# Power_Supply_Switching.net
KiCad netlist of a schematic drawn in Altium Designer
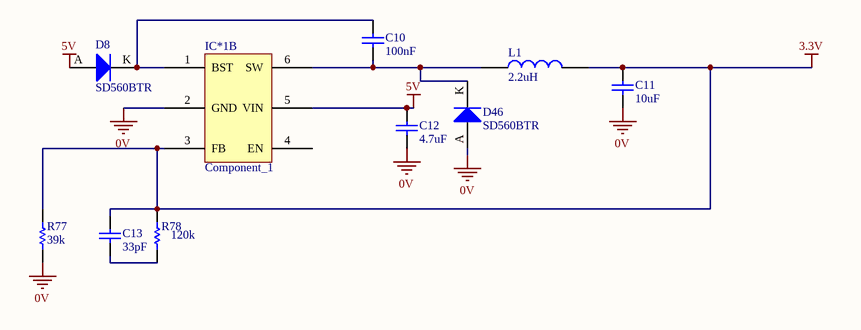
[diagram p0: Power Supply (Switching).SchDoc]

(export (version "E")
  (design (tool "Eeschema 10.0.6"))
  (components
    (comp (ref "C10")
      (value "100nF")
      (footprint "0805")
      (fields
        (field (name "PART NUMBER") "GCM21BR71E104KA37L")
        (field (name "TOLERANCE") "10%")
        (field (name "MANUFACTURER") "muRata")
      )
      (libsource (lib "ts_19-standard-library-IED") (part "Capacitor"))
    )
    (comp (ref "C11")
      (value "10uF")
      (footprint "0805")
      (fields
        (field (name "PART NUMBER") "GCM21BR61A106KA37L")
        (field (name "TOLERANCE") "10%")
        (field (name "MANUFACTURER") "muRata")
      )
      (libsource (lib "ts_19-standard-library-IED") (part "Capacitor"))
    )
    (comp (ref "C12")
      (value "4.7uF")
      (footprint "0805")
      (fields
        (field (name "PART NUMBER") "GCM21BR61A475KA37L")
        (field (name "TOLERANCE") "10%")
        (field (name "MANUFACTURER") "muRata")
      )
      (libsource (lib "ts_19-standard-library-IED") (part "Capacitor"))
    )
    (comp (ref "C13")
      (value "33pF")
      (footprint "0805")
      (fields
        (field (name "PART NUMBER") "GCM21B5C1H330JA37L")
        (field (name "TOLERANCE") "5%")
        (field (name "MANUFACTURER") "muRata")
      )
      (libsource (lib "ts_19-standard-library-IED") (part "Capacitor"))
    )
    (comp (ref "D8")
      (value "SD560BTR")
      (footprint "SMB Diode")
      (description "1.2V_F 600V 5A SMB")
      (fields
        (field (name "MANUFACTURER") "SMC Diode Solutions")
        (field (name "DIGIKEY PART NUMBER") "1655-1530-2-ND")
      )
      (libsource (lib "ts_19-standard-library") (part "Diode"))
    )
    (comp (ref "D46")
      (value "SD560BTR")
      (footprint "SMB Diode")
      (description "1.2V_F 600V 5A SMB")
      (fields
        (field (name "MANUFACTURER") "SMC Diode Solutions")
        (field (name "DIGIKEY PART NUMBER") "1655-1530-2-ND")
      )
      (libsource (lib "ts_19-standard-library") (part "Diode"))
    )
    (comp (ref "IC*1")
      (value "Component_1")
      (footprint "MP2451 SOT23-6")
      (description "MP2451")
      (libsource (lib "MP2451lib") (part "Component_1"))
    )
    (comp (ref "L1")
      (value "2.2uH")
      (footprint "1210")
      (fields
        (field (name "MANUFACTURER") "Murata")
        (field (name "PART NUMBER") "LQH32PN2R2NN0L")
        (field (name "TOLERANCE") "0.3")
      )
      (libsource (lib "ts_19-standard-library-IED") (part "Inductor"))
    )
    (comp (ref "R77")
      (value "39k")
      (footprint "0805")
      (fields
        (field (name "MANUFACTURER") "YAGEO")
        (field (name "PART NUMBER") "RC0805FR0739KL")
        (field (name "TOLERANCE") "0.01")
      )
      (libsource (lib "ts_19-standard-library-IED") (part "Resistor"))
    )
    (comp (ref "R78")
      (value "120k")
      (footprint "0805")
      (fields
        (field (name "MANUFACTURER") "YAGEO")
        (field (name "PART NUMBER") "RC0805FR07120KL")
        (field (name "TOLERANCE") "0.01")
      )
      (libsource (lib "ts_19-standard-library-IED") (part "Resistor"))
    )
  )
  (nets
    (net (code "1") (name "0V") (class "Default")
      (node (ref "C11") (pin "1") (pinfunction "1_1") (pintype "passive"))
      (node (ref "C12") (pin "1") (pinfunction "1_1") (pintype "passive"))
      (node (ref "D46") (pin "A") (pinfunction "A_A") (pintype "passive"))
      (node (ref "IC*1") (pin "2") (pinfunction "GND_2") (pintype "passive"))
      (node (ref "R77") (pin "1") (pinfunction "1_1") (pintype "passive"))
    )
    (net (code "2") (name "3.3V") (class "Default")
      (node (ref "C11") (pin "2") (pinfunction "2_2") (pintype "passive"))
      (node (ref "C13") (pin "2") (pinfunction "2_2") (pintype "passive"))
      (node (ref "IC*1") (pin "3") (pinfunction "FB_3") (pintype "passive"))
      (node (ref "L1") (pin "1") (pinfunction "1_1") (pintype "passive"))
      (node (ref "R77") (pin "2") (pinfunction "2_2") (pintype "passive"))
      (node (ref "R78") (pin "2") (pinfunction "2_2") (pintype "passive"))
    )
    (net (code "3") (name "5V") (class "Default")
      (node (ref "C12") (pin "2") (pinfunction "2_2") (pintype "passive"))
      (node (ref "D8") (pin "A") (pinfunction "A_A") (pintype "passive"))
      (node (ref "IC*1") (pin "5") (pinfunction "VIN_5") (pintype "passive"))
    )
    (net (code "4") (name "Net-(C13-Pad1)") (class "Default")
      (node (ref "C13") (pin "1") (pinfunction "1_1") (pintype "passive"))
      (node (ref "R78") (pin "1") (pinfunction "1_1") (pintype "passive"))
    )
    (net (code "5") (name "Net-(IC*1B-BST)") (class "Default")
      (node (ref "C10") (pin "1") (pinfunction "1_1") (pintype "passive"))
      (node (ref "D8") (pin "K") (pinfunction "K_K") (pintype "passive"))
      (node (ref "IC*1") (pin "1") (pinfunction "BST_1") (pintype "passive"))
    )
    (net (code "6") (name "Net-(IC*1B-SW)") (class "Default")
      (node (ref "C10") (pin "2") (pinfunction "2_2") (pintype "passive"))
      (node (ref "D46") (pin "K") (pinfunction "K_K") (pintype "passive"))
      (node (ref "IC*1") (pin "6") (pinfunction "SW_6") (pintype "passive"))
      (node (ref "L1") (pin "2") (pinfunction "2_2") (pintype "passive"))
    )
    (net (code "7") (name "unconnected-(IC*1B-EN-Pad4)") (class "Default")
      (node (ref "IC*1") (pin "4") (pinfunction "EN_4") (pintype "passive"))
    )
  )
)
